# Gyro_Board.net
KiCad netlist of a schematic drawn in EAGLE
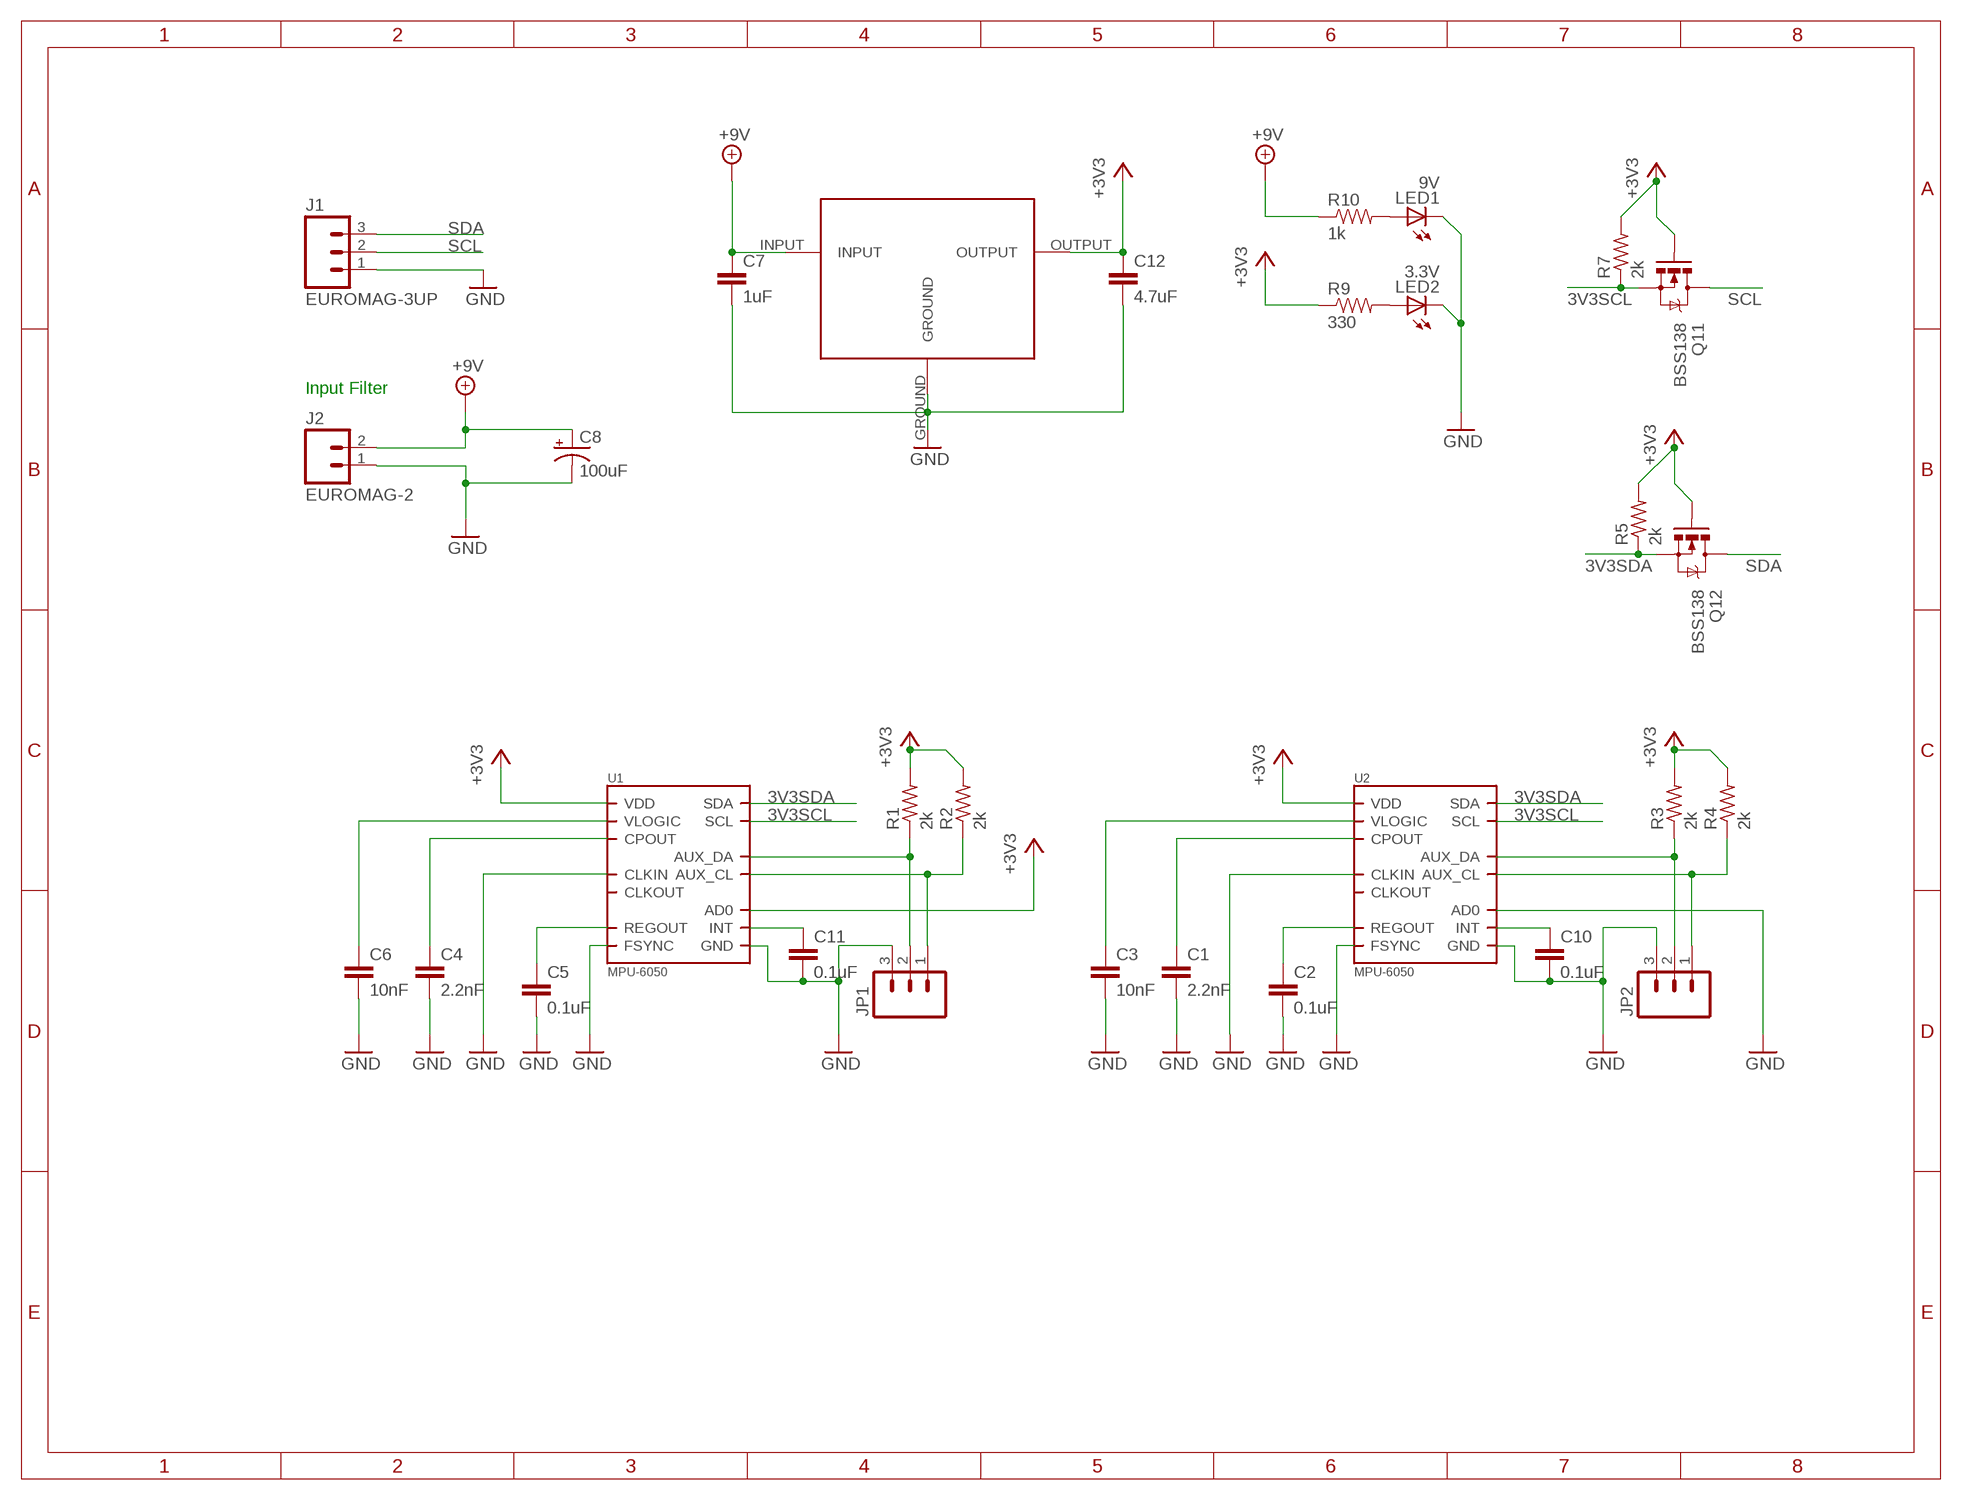
[diagram p0: schematic, sheet 1]

(export (version "E")
  (design (tool "Eeschema 10.0.6"))
  (components
    (comp (ref "3.3V")
      (value "LP2950")
      (footprint "eagle-import:TO-252")
      (libsource (lib "eagle-import") (part "LP2950"))
    )
    (comp (ref "C1")
      (value "2.2nF")
      (footprint "eagle-import:0805")
      (libsource (lib "eagle-import") (part "CAP0805"))
    )
    (comp (ref "C2")
      (value "0.1uF")
      (footprint "eagle-import:0805")
      (libsource (lib "eagle-import") (part "CAP0805"))
    )
    (comp (ref "C3")
      (value "10nF")
      (footprint "eagle-import:0805")
      (libsource (lib "eagle-import") (part "CAP0805"))
    )
    (comp (ref "C4")
      (value "2.2nF")
      (footprint "eagle-import:0805")
      (libsource (lib "eagle-import") (part "CAP0805"))
    )
    (comp (ref "C5")
      (value "0.1uF")
      (footprint "eagle-import:0805")
      (libsource (lib "eagle-import") (part "CAP0805"))
    )
    (comp (ref "C6")
      (value "10nF")
      (footprint "eagle-import:0805")
      (libsource (lib "eagle-import") (part "CAP0805"))
    )
    (comp (ref "C7")
      (value "1uF")
      (footprint "eagle-import:0805")
      (libsource (lib "eagle-import") (part "CAP0805"))
    )
    (comp (ref "C8")
      (value "100uF")
      (footprint "eagle-import:153CLV-0605")
      (libsource (lib "eagle-import") (part "CPOL-US153CLV-0605"))
    )
    (comp (ref "C10")
      (value "0.1uF")
      (footprint "eagle-import:0805")
      (libsource (lib "eagle-import") (part "CAP0805"))
    )
    (comp (ref "C11")
      (value "0.1uF")
      (footprint "eagle-import:0805")
      (libsource (lib "eagle-import") (part "CAP0805"))
    )
    (comp (ref "C12")
      (value "4.7uF")
      (footprint "eagle-import:0805")
      (libsource (lib "eagle-import") (part "CAP0805"))
    )
    (comp (ref "J1")
      (value "EUROMAG-3UP")
      (footprint "eagle-import:M3-UP")
      (libsource (lib "eagle-import") (part "EUROMAG-3UP"))
    )
    (comp (ref "J2")
      (value "EUROMAG-2")
      (footprint "eagle-import:M2-UP")
      (libsource (lib "eagle-import") (part "EUROMAG-2"))
    )
    (comp (ref "JP1")
      (value "M03LOCK")
      (footprint "eagle-import:1X03_LOCK")
      (libsource (lib "eagle-import") (part "M03LOCK"))
    )
    (comp (ref "JP2")
      (value "M03LOCK")
      (footprint "eagle-import:1X03_LOCK")
      (libsource (lib "eagle-import") (part "M03LOCK"))
    )
    (comp (ref "LED1")
      (value "9V")
      (footprint "eagle-import:CHIP-LED0805")
      (libsource (lib "eagle-import") (part "LEDCHIP-LED0805"))
    )
    (comp (ref "LED2")
      (value "3.3V")
      (footprint "eagle-import:CHIP-LED0805")
      (libsource (lib "eagle-import") (part "LEDCHIP-LED0805"))
    )
    (comp (ref "Q11")
      (value "BSS138")
      (footprint "eagle-import:SOT23-3")
      (libsource (lib "eagle-import") (part "MOSFET-NCHANNELSMD"))
    )
    (comp (ref "Q12")
      (value "BSS138")
      (footprint "eagle-import:SOT23-3")
      (libsource (lib "eagle-import") (part "MOSFET-NCHANNELSMD"))
    )
    (comp (ref "R1")
      (value "2k")
      (footprint "eagle-import:M0805")
      (libsource (lib "eagle-import") (part "R-US_M0805"))
    )
    (comp (ref "R2")
      (value "2k")
      (footprint "eagle-import:M0805")
      (libsource (lib "eagle-import") (part "R-US_M0805"))
    )
    (comp (ref "R3")
      (value "2k")
      (footprint "eagle-import:M0805")
      (libsource (lib "eagle-import") (part "R-US_M0805"))
    )
    (comp (ref "R4")
      (value "2k")
      (footprint "eagle-import:M0805")
      (libsource (lib "eagle-import") (part "R-US_M0805"))
    )
    (comp (ref "R5")
      (value "2k")
      (footprint "eagle-import:R0805")
      (libsource (lib "eagle-import") (part "R-US_R0805"))
    )
    (comp (ref "R7")
      (value "2k")
      (footprint "eagle-import:R0805")
      (libsource (lib "eagle-import") (part "R-US_R0805"))
    )
    (comp (ref "R9")
      (value "330")
      (footprint "eagle-import:0805")
      (libsource (lib "eagle-import") (part "RESISTOR0805-RES"))
    )
    (comp (ref "R10")
      (value "1k")
      (footprint "eagle-import:0805")
      (libsource (lib "eagle-import") (part "RESISTOR0805-RES"))
    )
    (comp (ref "U1")
      (value "MPU-6050")
      (footprint "eagle-import:QFN.24.4X4")
      (libsource (lib "eagle-import") (part "MPU-6050"))
    )
    (comp (ref "U2")
      (value "MPU-6050")
      (footprint "eagle-import:QFN.24.4X4")
      (libsource (lib "eagle-import") (part "MPU-6050"))
    )
  )
  (nets
    (net (code "1") (name "+3V3") (class "Default")
      (node (ref "3.3V") (pin "OUTPUT") (pinfunction "OUTPUT_OUTPUT") (pintype "bidirectional"))
      (node (ref "C12") (pin "1") (pinfunction "1_1") (pintype "passive"))
      (node (ref "Q11") (pin "1") (pinfunction "G_1") (pintype "passive"))
      (node (ref "Q12") (pin "1") (pinfunction "G_1") (pintype "passive"))
      (node (ref "R1") (pin "2") (pinfunction "2_2") (pintype "passive"))
      (node (ref "R2") (pin "2") (pinfunction "2_2") (pintype "passive"))
      (node (ref "R3") (pin "2") (pinfunction "2_2") (pintype "passive"))
      (node (ref "R4") (pin "2") (pinfunction "2_2") (pintype "passive"))
      (node (ref "R5") (pin "2") (pinfunction "2_2") (pintype "passive"))
      (node (ref "R7") (pin "2") (pinfunction "2_2") (pintype "passive"))
      (node (ref "R9") (pin "1") (pinfunction "1_1") (pintype "passive"))
      (node (ref "U1") (pin "13") (pinfunction "VDD_13") (pintype "bidirectional"))
      (node (ref "U1") (pin "9") (pinfunction "AD0_9") (pintype "bidirectional"))
      (node (ref "U2") (pin "13") (pinfunction "VDD_13") (pintype "bidirectional"))
    )
    (net (code "2") (name "+9V") (class "Default")
      (node (ref "3.3V") (pin "INPUT") (pinfunction "INPUT_INPUT") (pintype "bidirectional"))
      (node (ref "C7") (pin "1") (pinfunction "1_1") (pintype "passive"))
      (node (ref "C8") (pin "+") (pinfunction "+_+") (pintype "passive"))
      (node (ref "J2") (pin "2") (pinfunction "2_2") (pintype "passive"))
      (node (ref "R10") (pin "1") (pinfunction "1_1") (pintype "passive"))
    )
    (net (code "3") (name "/3V3SCL") (class "Default")
      (node (ref "Q11") (pin "2") (pinfunction "S_2") (pintype "passive"))
      (node (ref "R7") (pin "1") (pinfunction "1_1") (pintype "passive"))
      (node (ref "U1") (pin "23") (pinfunction "SCL_23") (pintype "bidirectional"))
      (node (ref "U2") (pin "23") (pinfunction "SCL_23") (pintype "bidirectional"))
    )
    (net (code "4") (name "/3V3SDA") (class "Default")
      (node (ref "Q12") (pin "2") (pinfunction "S_2") (pintype "passive"))
      (node (ref "R5") (pin "1") (pinfunction "1_1") (pintype "passive"))
      (node (ref "U1") (pin "24") (pinfunction "SDA_24") (pintype "bidirectional"))
      (node (ref "U2") (pin "24") (pinfunction "SDA_24") (pintype "bidirectional"))
    )
    (net (code "5") (name "/SCL") (class "Default")
      (node (ref "J1") (pin "2") (pinfunction "2_2") (pintype "passive"))
      (node (ref "Q11") (pin "3") (pinfunction "D_3") (pintype "passive"))
    )
    (net (code "6") (name "/SDA") (class "Default")
      (node (ref "J1") (pin "3") (pinfunction "3_3") (pintype "passive"))
      (node (ref "Q12") (pin "3") (pinfunction "D_3") (pintype "passive"))
    )
    (net (code "7") (name "GND") (class "Default")
      (node (ref "3.3V") (pin "GROUND") (pinfunction "GROUND_GROUND") (pintype "bidirectional"))
      (node (ref "C1") (pin "2") (pinfunction "2_2") (pintype "passive"))
      (node (ref "C10") (pin "2") (pinfunction "2_2") (pintype "passive"))
      (node (ref "C11") (pin "2") (pinfunction "2_2") (pintype "passive"))
      (node (ref "C12") (pin "2") (pinfunction "2_2") (pintype "passive"))
      (node (ref "C2") (pin "2") (pinfunction "2_2") (pintype "passive"))
      (node (ref "C3") (pin "2") (pinfunction "2_2") (pintype "passive"))
      (node (ref "C4") (pin "2") (pinfunction "2_2") (pintype "passive"))
      (node (ref "C5") (pin "2") (pinfunction "2_2") (pintype "passive"))
      (node (ref "C6") (pin "2") (pinfunction "2_2") (pintype "passive"))
      (node (ref "C7") (pin "2") (pinfunction "2_2") (pintype "passive"))
      (node (ref "C8") (pin "-") (pinfunction "-_-") (pintype "passive"))
      (node (ref "J1") (pin "1") (pinfunction "1_1") (pintype "passive"))
      (node (ref "J2") (pin "1") (pinfunction "1_1") (pintype "passive"))
      (node (ref "JP1") (pin "3") (pinfunction "3_3") (pintype "passive"))
      (node (ref "JP2") (pin "3") (pinfunction "3_3") (pintype "passive"))
      (node (ref "LED1") (pin "C") (pinfunction "C_C") (pintype "passive"))
      (node (ref "LED2") (pin "C") (pinfunction "C_C") (pintype "passive"))
      (node (ref "U1") (pin "1") (pinfunction "CLKIN_1") (pintype "bidirectional"))
      (node (ref "U1") (pin "11") (pinfunction "FSYNC_11") (pintype "bidirectional"))
      (node (ref "U1") (pin "18") (pinfunction "GND_18") (pintype "bidirectional"))
      (node (ref "U2") (pin "1") (pinfunction "CLKIN_1") (pintype "bidirectional"))
      (node (ref "U2") (pin "11") (pinfunction "FSYNC_11") (pintype "bidirectional"))
      (node (ref "U2") (pin "18") (pinfunction "GND_18") (pintype "bidirectional"))
      (node (ref "U2") (pin "9") (pinfunction "AD0_9") (pintype "bidirectional"))
    )
    (net (code "8") (name "Net-(LED1-PadA)") (class "Default")
      (node (ref "LED1") (pin "A") (pinfunction "A_A") (pintype "passive"))
      (node (ref "R10") (pin "2") (pinfunction "2_2") (pintype "passive"))
    )
    (net (code "9") (name "Net-(LED2-PadA)") (class "Default")
      (node (ref "LED2") (pin "A") (pinfunction "A_A") (pintype "passive"))
      (node (ref "R9") (pin "2") (pinfunction "2_2") (pintype "passive"))
    )
    (net (code "10") (name "Net-(U1-AUX_CL)") (class "Default")
      (node (ref "JP1") (pin "1") (pinfunction "1_1") (pintype "passive"))
      (node (ref "R2") (pin "1") (pinfunction "1_1") (pintype "passive"))
      (node (ref "U1") (pin "7") (pinfunction "AUX_CL_7") (pintype "bidirectional"))
    )
    (net (code "11") (name "Net-(U1-AUX_DA)") (class "Default")
      (node (ref "JP1") (pin "2") (pinfunction "2_2") (pintype "passive"))
      (node (ref "R1") (pin "1") (pinfunction "1_1") (pintype "passive"))
      (node (ref "U1") (pin "6") (pinfunction "AUX_DA_6") (pintype "bidirectional"))
    )
    (net (code "12") (name "Net-(U1-CPOUT)") (class "Default")
      (node (ref "C4") (pin "1") (pinfunction "1_1") (pintype "passive"))
      (node (ref "U1") (pin "20") (pinfunction "CPOUT_20") (pintype "bidirectional"))
    )
    (net (code "13") (name "Net-(U1-INT)") (class "Default")
      (node (ref "C11") (pin "1") (pinfunction "1_1") (pintype "passive"))
      (node (ref "U1") (pin "12") (pinfunction "INT_12") (pintype "bidirectional"))
    )
    (net (code "14") (name "Net-(U1-REGOUT)") (class "Default")
      (node (ref "C5") (pin "1") (pinfunction "1_1") (pintype "passive"))
      (node (ref "U1") (pin "10") (pinfunction "REGOUT_10") (pintype "bidirectional"))
    )
    (net (code "15") (name "Net-(U1-VLOGIC)") (class "Default")
      (node (ref "C6") (pin "1") (pinfunction "1_1") (pintype "passive"))
      (node (ref "U1") (pin "8") (pinfunction "VLOGIC_8") (pintype "bidirectional"))
    )
    (net (code "16") (name "Net-(U2-AUX_CL)") (class "Default")
      (node (ref "JP2") (pin "1") (pinfunction "1_1") (pintype "passive"))
      (node (ref "R4") (pin "1") (pinfunction "1_1") (pintype "passive"))
      (node (ref "U2") (pin "7") (pinfunction "AUX_CL_7") (pintype "bidirectional"))
    )
    (net (code "17") (name "Net-(U2-AUX_DA)") (class "Default")
      (node (ref "JP2") (pin "2") (pinfunction "2_2") (pintype "passive"))
      (node (ref "R3") (pin "1") (pinfunction "1_1") (pintype "passive"))
      (node (ref "U2") (pin "6") (pinfunction "AUX_DA_6") (pintype "bidirectional"))
    )
    (net (code "18") (name "Net-(U2-CPOUT)") (class "Default")
      (node (ref "C1") (pin "1") (pinfunction "1_1") (pintype "passive"))
      (node (ref "U2") (pin "20") (pinfunction "CPOUT_20") (pintype "bidirectional"))
    )
    (net (code "19") (name "Net-(U2-INT)") (class "Default")
      (node (ref "C10") (pin "1") (pinfunction "1_1") (pintype "passive"))
      (node (ref "U2") (pin "12") (pinfunction "INT_12") (pintype "bidirectional"))
    )
    (net (code "20") (name "Net-(U2-REGOUT)") (class "Default")
      (node (ref "C2") (pin "1") (pinfunction "1_1") (pintype "passive"))
      (node (ref "U2") (pin "10") (pinfunction "REGOUT_10") (pintype "bidirectional"))
    )
    (net (code "21") (name "Net-(U2-VLOGIC)") (class "Default")
      (node (ref "C3") (pin "1") (pinfunction "1_1") (pintype "passive"))
      (node (ref "U2") (pin "8") (pinfunction "VLOGIC_8") (pintype "bidirectional"))
    )
    (net (code "22") (name "unconnected-(U1-CLKOUT-Pad22)") (class "Default")
      (node (ref "U1") (pin "22") (pinfunction "CLKOUT_22") (pintype "bidirectional"))
    )
    (net (code "23") (name "unconnected-(U2-CLKOUT-Pad22)") (class "Default")
      (node (ref "U2") (pin "22") (pinfunction "CLKOUT_22") (pintype "bidirectional"))
    )
  )
)
